# led_buttons-2.net
KiCad netlist of a schematic drawn in EAGLE
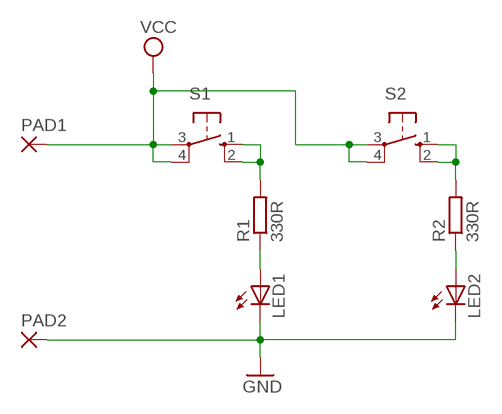
[diagram p0: schematic, sheet 1]

(export (version "E")
  (design (tool "Eeschema 10.0.6"))
  (components
    (comp (ref "LED1")
      (value "LEDCHIP-LED0603")
      (footprint "eagle-import:CHIP-LED0603")
      (libsource (lib "eagle-import") (part "LEDCHIP-LED0603"))
    )
    (comp (ref "LED2")
      (value "LEDCHIP-LED0603")
      (footprint "eagle-import:CHIP-LED0603")
      (libsource (lib "eagle-import") (part "LEDCHIP-LED0603"))
    )
    (comp (ref "PAD1")
      (value "SMD5")
      (footprint "eagle-import:SMD2,54-5,08")
      (libsource (lib "eagle-import") (part "SMD5"))
    )
    (comp (ref "PAD2")
      (value "SMD5")
      (footprint "eagle-import:SMD2,54-5,08")
      (libsource (lib "eagle-import") (part "SMD5"))
    )
    (comp (ref "R1")
      (value "330R")
      (footprint "eagle-import:R0603")
      (libsource (lib "eagle-import") (part "R-EU_R0603"))
    )
    (comp (ref "R2")
      (value "330R")
      (footprint "eagle-import:R0603")
      (libsource (lib "eagle-import") (part "R-EU_R0603"))
    )
    (comp (ref "S1")
      (value "10-XX")
      (footprint "eagle-import:B3F-10XX")
      (fields (field (name "MPN") "B3F-1000"))
      (libsource (lib "eagle-import") (part "10-XX"))
    )
    (comp (ref "S2")
      (value "10-XX")
      (footprint "eagle-import:B3F-10XX")
      (fields (field (name "MPN") "B3F-1000"))
      (libsource (lib "eagle-import") (part "10-XX"))
    )
  )
  (nets
    (net (code "1") (name "GND") (class "Default")
      (node (ref "LED1") (pin "C") (pinfunction "C_C") (pintype "passive"))
      (node (ref "LED2") (pin "C") (pinfunction "C_C") (pintype "passive"))
      (node (ref "PAD2") (pin "1") (pinfunction "P_1") (pintype "passive"))
    )
    (net (code "2") (name "Net-(LED1-PadA)") (class "Default")
      (node (ref "LED1") (pin "A") (pinfunction "A_A") (pintype "passive"))
      (node (ref "R1") (pin "1") (pinfunction "1_1") (pintype "passive"))
    )
    (net (code "3") (name "Net-(LED2-PadA)") (class "Default")
      (node (ref "LED2") (pin "A") (pinfunction "A_A") (pintype "passive"))
      (node (ref "R2") (pin "1") (pinfunction "1_1") (pintype "passive"))
    )
    (net (code "4") (name "Net-(S1-S)") (class "Default")
      (node (ref "R1") (pin "2") (pinfunction "2_2") (pintype "passive"))
      (node (ref "S1") (pin "1") (pinfunction "S_1") (pintype "passive"))
      (node (ref "S1") (pin "2") (pinfunction "S1_2") (pintype "passive"))
    )
    (net (code "5") (name "Net-(S2-S)") (class "Default")
      (node (ref "R2") (pin "2") (pinfunction "2_2") (pintype "passive"))
      (node (ref "S2") (pin "1") (pinfunction "S_1") (pintype "passive"))
      (node (ref "S2") (pin "2") (pinfunction "S1_2") (pintype "passive"))
    )
    (net (code "6") (name "VCC") (class "Default")
      (node (ref "PAD1") (pin "1") (pinfunction "P_1") (pintype "passive"))
      (node (ref "S1") (pin "3") (pinfunction "P_3") (pintype "passive"))
      (node (ref "S1") (pin "4") (pinfunction "P1_4") (pintype "passive"))
      (node (ref "S2") (pin "3") (pinfunction "P_3") (pintype "passive"))
      (node (ref "S2") (pin "4") (pinfunction "P1_4") (pintype "passive"))
    )
  )
)
